# mega8.net
KiCad netlist of a schematic drawn in EAGLE
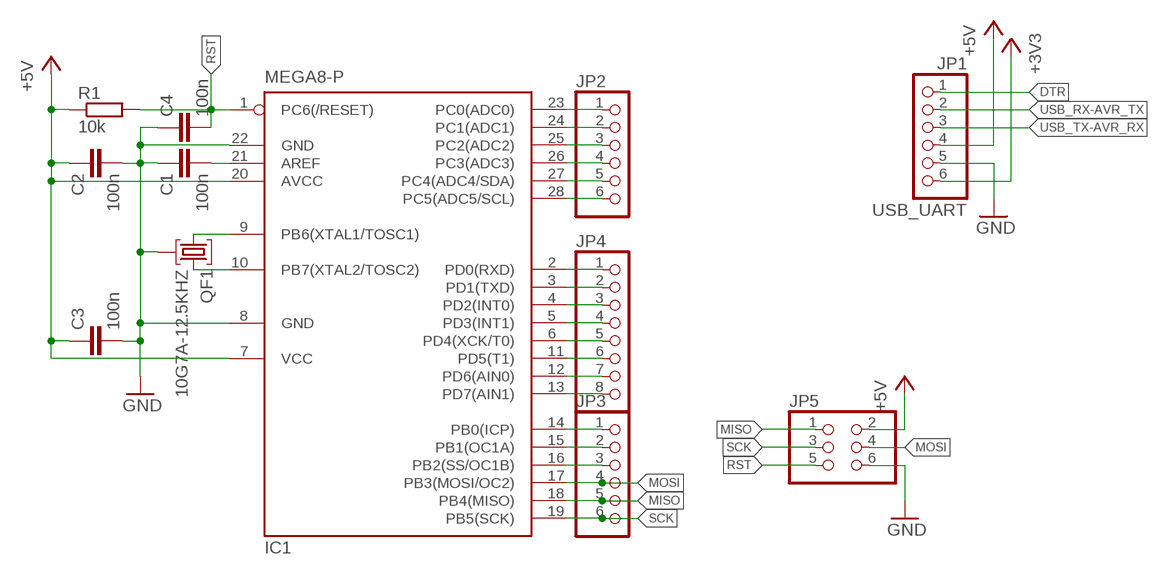
[diagram p0: schematic, sheet 1]

(export (version "E")
  (design (tool "Eeschema 10.0.6"))
  (components
    (comp (ref "C1")
      (value "100n")
      (footprint "eagle-import:C0603")
      (libsource (lib "eagle-import") (part "C-EUC0603"))
    )
    (comp (ref "C2")
      (value "100n")
      (footprint "eagle-import:C0603")
      (libsource (lib "eagle-import") (part "C-EUC0603"))
    )
    (comp (ref "C3")
      (value "100n")
      (footprint "eagle-import:C0603")
      (libsource (lib "eagle-import") (part "C-EUC0603"))
    )
    (comp (ref "C4")
      (value "100n")
      (footprint "eagle-import:C0603")
      (libsource (lib "eagle-import") (part "C-EUC0603"))
    )
    (comp (ref "IC1")
      (value "MEGA8-P")
      (footprint "eagle-import:DIL28-3")
      (libsource (lib "eagle-import") (part "MEGA8-P"))
    )
    (comp (ref "JP1")
      (value "USB_UART")
      (footprint "eagle-import:1X06")
      (libsource (lib "eagle-import") (part "PINHD-1X6"))
    )
    (comp (ref "JP2")
      (value "PINHD-1X6")
      (footprint "eagle-import:1X06")
      (libsource (lib "eagle-import") (part "PINHD-1X6"))
    )
    (comp (ref "JP3")
      (value "PINHD-1X6")
      (footprint "eagle-import:1X06")
      (libsource (lib "eagle-import") (part "PINHD-1X6"))
    )
    (comp (ref "JP4")
      (value "PINHD-1X8")
      (footprint "eagle-import:1X08")
      (libsource (lib "eagle-import") (part "PINHD-1X8"))
    )
    (comp (ref "JP5")
      (value "PINHD-2X3")
      (footprint "eagle-import:2X03")
      (libsource (lib "eagle-import") (part "PINHD-2X3"))
    )
    (comp (ref "QF1")
      (value "10G7A-12.5KHZ")
      (footprint "eagle-import:HC49U")
      (libsource (lib "eagle-import") (part "10G7A-12.5KHZ"))
    )
    (comp (ref "R1")
      (value "10k")
      (footprint "eagle-import:R0603")
      (libsource (lib "eagle-import") (part "R-EU_R0603"))
    )
  )
  (nets
    (net (code "1") (name "+3V3") (class "Default")
      (node (ref "JP1") (pin "6") (pinfunction "6_6") (pintype "passive"))
    )
    (net (code "2") (name "+5V") (class "Default")
      (node (ref "C2") (pin "1") (pinfunction "1_1") (pintype "passive"))
      (node (ref "C3") (pin "1") (pinfunction "1_1") (pintype "passive"))
      (node (ref "IC1") (pin "20") (pinfunction "AVCC_20") (pintype "power_in"))
      (node (ref "IC1") (pin "7") (pinfunction "VCC_7") (pintype "power_in"))
      (node (ref "JP1") (pin "4") (pinfunction "4_4") (pintype "passive"))
      (node (ref "JP5") (pin "2") (pinfunction "2_2") (pintype "passive"))
      (node (ref "R1") (pin "1") (pinfunction "1_1") (pintype "passive"))
    )
    (net (code "3") (name "DTR") (class "Default")
      (node (ref "JP1") (pin "1") (pinfunction "1_1") (pintype "passive"))
    )
    (net (code "4") (name "GND") (class "Default")
      (node (ref "C1") (pin "1") (pinfunction "1_1") (pintype "passive"))
      (node (ref "C2") (pin "2") (pinfunction "2_2") (pintype "passive"))
      (node (ref "C3") (pin "2") (pinfunction "2_2") (pintype "passive"))
      (node (ref "C4") (pin "1") (pinfunction "1_1") (pintype "passive"))
      (node (ref "IC1") (pin "22") (pinfunction "GND_22") (pintype "power_in"))
      (node (ref "IC1") (pin "8") (pinfunction "GND_8") (pintype "power_in"))
      (node (ref "JP1") (pin "5") (pinfunction "5_5") (pintype "passive"))
      (node (ref "JP5") (pin "6") (pinfunction "6_6") (pintype "passive"))
      (node (ref "QF1") (pin "2") (pinfunction "2_2") (pintype "passive"))
    )
    (net (code "5") (name "MISO") (class "Default")
      (node (ref "IC1") (pin "18") (pinfunction "PB4(MISO)_18") (pintype "bidirectional"))
      (node (ref "JP3") (pin "5") (pinfunction "5_5") (pintype "passive"))
      (node (ref "JP5") (pin "1") (pinfunction "1_1") (pintype "passive"))
    )
    (net (code "6") (name "MOSI") (class "Default")
      (node (ref "IC1") (pin "17") (pinfunction "PB3(MOSI/OC2)_17") (pintype "bidirectional"))
      (node (ref "JP3") (pin "4") (pinfunction "4_4") (pintype "passive"))
      (node (ref "JP5") (pin "4") (pinfunction "4_4") (pintype "passive"))
    )
    (net (code "7") (name "Net-(IC1-AREF)") (class "Default")
      (node (ref "C1") (pin "2") (pinfunction "2_2") (pintype "passive"))
      (node (ref "IC1") (pin "21") (pinfunction "AREF_21") (pintype "passive"))
    )
    (net (code "8") (name "Net-(IC1-PB0(ICP))") (class "Default")
      (node (ref "IC1") (pin "14") (pinfunction "PB0(ICP)_14") (pintype "bidirectional"))
      (node (ref "JP3") (pin "1") (pinfunction "1_1") (pintype "passive"))
    )
    (net (code "9") (name "Net-(IC1-PB1(OC1A))") (class "Default")
      (node (ref "IC1") (pin "15") (pinfunction "PB1(OC1A)_15") (pintype "bidirectional"))
      (node (ref "JP3") (pin "2") (pinfunction "2_2") (pintype "passive"))
    )
    (net (code "10") (name "Net-(IC1-PB2(SS{slash}OC1B))") (class "Default")
      (node (ref "IC1") (pin "16") (pinfunction "PB2(SS/OC1B)_16") (pintype "bidirectional"))
      (node (ref "JP3") (pin "3") (pinfunction "3_3") (pintype "passive"))
    )
    (net (code "11") (name "Net-(IC1-PB6(XTAL1{slash}TOSC1))") (class "Default")
      (node (ref "IC1") (pin "9") (pinfunction "PB6(XTAL1/TOSC1)_9") (pintype "bidirectional"))
      (node (ref "QF1") (pin "1") (pinfunction "1_1") (pintype "passive"))
    )
    (net (code "12") (name "Net-(IC1-PB7(XTAL2{slash}TOSC2))") (class "Default")
      (node (ref "IC1") (pin "10") (pinfunction "PB7(XTAL2/TOSC2)_10") (pintype "bidirectional"))
      (node (ref "QF1") (pin "3") (pinfunction "3_3") (pintype "passive"))
    )
    (net (code "13") (name "Net-(IC1-PC0(ADC0))") (class "Default")
      (node (ref "IC1") (pin "23") (pinfunction "PC0(ADC0)_23") (pintype "bidirectional"))
      (node (ref "JP2") (pin "1") (pinfunction "1_1") (pintype "passive"))
    )
    (net (code "14") (name "Net-(IC1-PC1(ADC1))") (class "Default")
      (node (ref "IC1") (pin "24") (pinfunction "PC1(ADC1)_24") (pintype "bidirectional"))
      (node (ref "JP2") (pin "2") (pinfunction "2_2") (pintype "passive"))
    )
    (net (code "15") (name "Net-(IC1-PC2(ADC2))") (class "Default")
      (node (ref "IC1") (pin "25") (pinfunction "PC2(ADC2)_25") (pintype "bidirectional"))
      (node (ref "JP2") (pin "3") (pinfunction "3_3") (pintype "passive"))
    )
    (net (code "16") (name "Net-(IC1-PC3(ADC3))") (class "Default")
      (node (ref "IC1") (pin "26") (pinfunction "PC3(ADC3)_26") (pintype "bidirectional"))
      (node (ref "JP2") (pin "4") (pinfunction "4_4") (pintype "passive"))
    )
    (net (code "17") (name "Net-(IC1-PC4(ADC4{slash}SDA))") (class "Default")
      (node (ref "IC1") (pin "27") (pinfunction "PC4(ADC4/SDA)_27") (pintype "bidirectional"))
      (node (ref "JP2") (pin "5") (pinfunction "5_5") (pintype "passive"))
    )
    (net (code "18") (name "Net-(IC1-PC5(ADC5{slash}SCL))") (class "Default")
      (node (ref "IC1") (pin "28") (pinfunction "PC5(ADC5/SCL)_28") (pintype "bidirectional"))
      (node (ref "JP2") (pin "6") (pinfunction "6_6") (pintype "passive"))
    )
    (net (code "19") (name "Net-(IC1-PD0(RXD))") (class "Default")
      (node (ref "IC1") (pin "2") (pinfunction "PD0(RXD)_2") (pintype "bidirectional"))
      (node (ref "JP4") (pin "1") (pinfunction "1_1") (pintype "passive"))
    )
    (net (code "20") (name "Net-(IC1-PD1(TXD))") (class "Default")
      (node (ref "IC1") (pin "3") (pinfunction "PD1(TXD)_3") (pintype "bidirectional"))
      (node (ref "JP4") (pin "2") (pinfunction "2_2") (pintype "passive"))
    )
    (net (code "21") (name "Net-(IC1-PD2(INT0))") (class "Default")
      (node (ref "IC1") (pin "4") (pinfunction "PD2(INT0)_4") (pintype "bidirectional"))
      (node (ref "JP4") (pin "3") (pinfunction "3_3") (pintype "passive"))
    )
    (net (code "22") (name "Net-(IC1-PD3(INT1))") (class "Default")
      (node (ref "IC1") (pin "5") (pinfunction "PD3(INT1)_5") (pintype "bidirectional"))
      (node (ref "JP4") (pin "4") (pinfunction "4_4") (pintype "passive"))
    )
    (net (code "23") (name "Net-(IC1-PD4(XCK{slash}T0))") (class "Default")
      (node (ref "IC1") (pin "6") (pinfunction "PD4(XCK/T0)_6") (pintype "bidirectional"))
      (node (ref "JP4") (pin "5") (pinfunction "5_5") (pintype "passive"))
    )
    (net (code "24") (name "Net-(IC1-PD5(T1))") (class "Default")
      (node (ref "IC1") (pin "11") (pinfunction "PD5(T1)_11") (pintype "bidirectional"))
      (node (ref "JP4") (pin "6") (pinfunction "6_6") (pintype "passive"))
    )
    (net (code "25") (name "Net-(IC1-PD6(AIN0))") (class "Default")
      (node (ref "IC1") (pin "12") (pinfunction "PD6(AIN0)_12") (pintype "bidirectional"))
      (node (ref "JP4") (pin "7") (pinfunction "7_7") (pintype "passive"))
    )
    (net (code "26") (name "Net-(IC1-PD7(AIN1))") (class "Default")
      (node (ref "IC1") (pin "13") (pinfunction "PD7(AIN1)_13") (pintype "bidirectional"))
      (node (ref "JP4") (pin "8") (pinfunction "8_8") (pintype "passive"))
    )
    (net (code "27") (name "RST") (class "Default")
      (node (ref "C4") (pin "2") (pinfunction "2_2") (pintype "passive"))
      (node (ref "IC1") (pin "1") (pinfunction "PC6(/RESET)_1") (pintype "bidirectional"))
      (node (ref "JP5") (pin "5") (pinfunction "5_5") (pintype "passive"))
      (node (ref "R1") (pin "2") (pinfunction "2_2") (pintype "passive"))
    )
    (net (code "28") (name "SCK") (class "Default")
      (node (ref "IC1") (pin "19") (pinfunction "PB5(SCK)_19") (pintype "bidirectional"))
      (node (ref "JP3") (pin "6") (pinfunction "6_6") (pintype "passive"))
      (node (ref "JP5") (pin "3") (pinfunction "3_3") (pintype "passive"))
    )
    (net (code "29") (name "USB_RX-AVR_TX") (class "Default")
      (node (ref "JP1") (pin "2") (pinfunction "2_2") (pintype "passive"))
    )
    (net (code "30") (name "USB_TX-AVR_RX") (class "Default")
      (node (ref "JP1") (pin "3") (pinfunction "3_3") (pintype "passive"))
    )
  )
)
